# RF-PCBF-2G4.net
KiCad netlist of a schematic drawn in Altium Designer
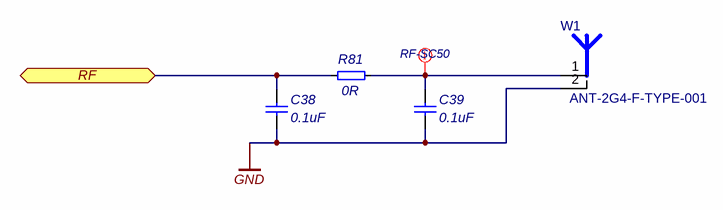
[diagram p0: RF-PCBF-2G4.SchDoc]

(export (version "E")
  (design (tool "Eeschema 10.0.6"))
  (components
    (comp (ref "C38")
      (value "0.1uF")
      (footprint "C0402")
      (fields
        (field (name "PART NUMBER") "0402-X5R-50V-0.1uF±10%")
        (field (name "VOLTAGE") "50V")
        (field (name "TOLERANCE") "10%")
      )
      (libsource (lib "ATB") (part "C"))
    )
    (comp (ref "C39")
      (value "0.1uF")
      (footprint "C0402")
      (fields
        (field (name "PART NUMBER") "0402-X5R-50V-0.1uF±10%")
        (field (name "VOLTAGE") "50V")
        (field (name "TOLERANCE") "10%")
      )
      (libsource (lib "ATB") (part "C"))
    )
    (comp (ref "R81")
      (value "0R")
      (footprint "R_0402")
      (fields
        (field (name "PART NUMBER") "0402-0.0625W-0R-100ppm±1%")
        (field (name "TOLERANCE") "1%")
        (field (name "MANUFACTURER") "Yageo")
      )
      (libsource (lib "ATB") (part "R"))
    )
    (comp (ref "W1")
      (value "ANT-2G4-F-TYPE-001")
      (footprint "ANT-2G4-F-TYPE-001")
      (description "Antenna")
      (libsource (lib "ATB") (part "ANT-2G4-F-TYPE-001"))
    )
  )
  (nets
    (net (code "1") (name "/RF") (class "Default")
      (node (ref "C38") (pin "2") (pinfunction "2_2") (pintype "passive"))
      (node (ref "R81") (pin "1") (pinfunction "1_1") (pintype "passive"))
    )
    (net (code "2") (name "GND") (class "Default")
      (node (ref "C38") (pin "1") (pinfunction "1_1") (pintype "passive"))
      (node (ref "C39") (pin "1") (pinfunction "1_1") (pintype "passive"))
      (node (ref "W1") (pin "2") (pinfunction "Out_2") (pintype "passive"))
    )
    (net (code "3") (name "Net-(C39-Pad2)") (class "Default")
      (node (ref "C39") (pin "2") (pinfunction "2_2") (pintype "passive"))
      (node (ref "R81") (pin "2") (pinfunction "2_2") (pintype "passive"))
      (node (ref "W1") (pin "1") (pinfunction "Out_1") (pintype "passive"))
    )
    (net (code "4") (name "unconnected-(W1-Fix_pad_2-Pad2)") (class "Default")
      (node (ref "W1") (pin "2") (pinfunction "Fix_pad_2_2") (pintype "passive"))
    )
    (net (code "5") (name "unconnected-(W1-Fix_pad_3-Pad3)") (class "Default")
      (node (ref "W1") (pin "3") (pinfunction "Fix_pad_3_3") (pintype "passive"))
    )
    (net (code "6") (name "unconnected-(W1-Fix_pad_4-Pad4)") (class "Default")
      (node (ref "W1") (pin "4") (pinfunction "Fix_pad_4_4") (pintype "passive"))
    )
  )
)
